# CPU.net
KiCad netlist of a schematic drawn in Altium Designer
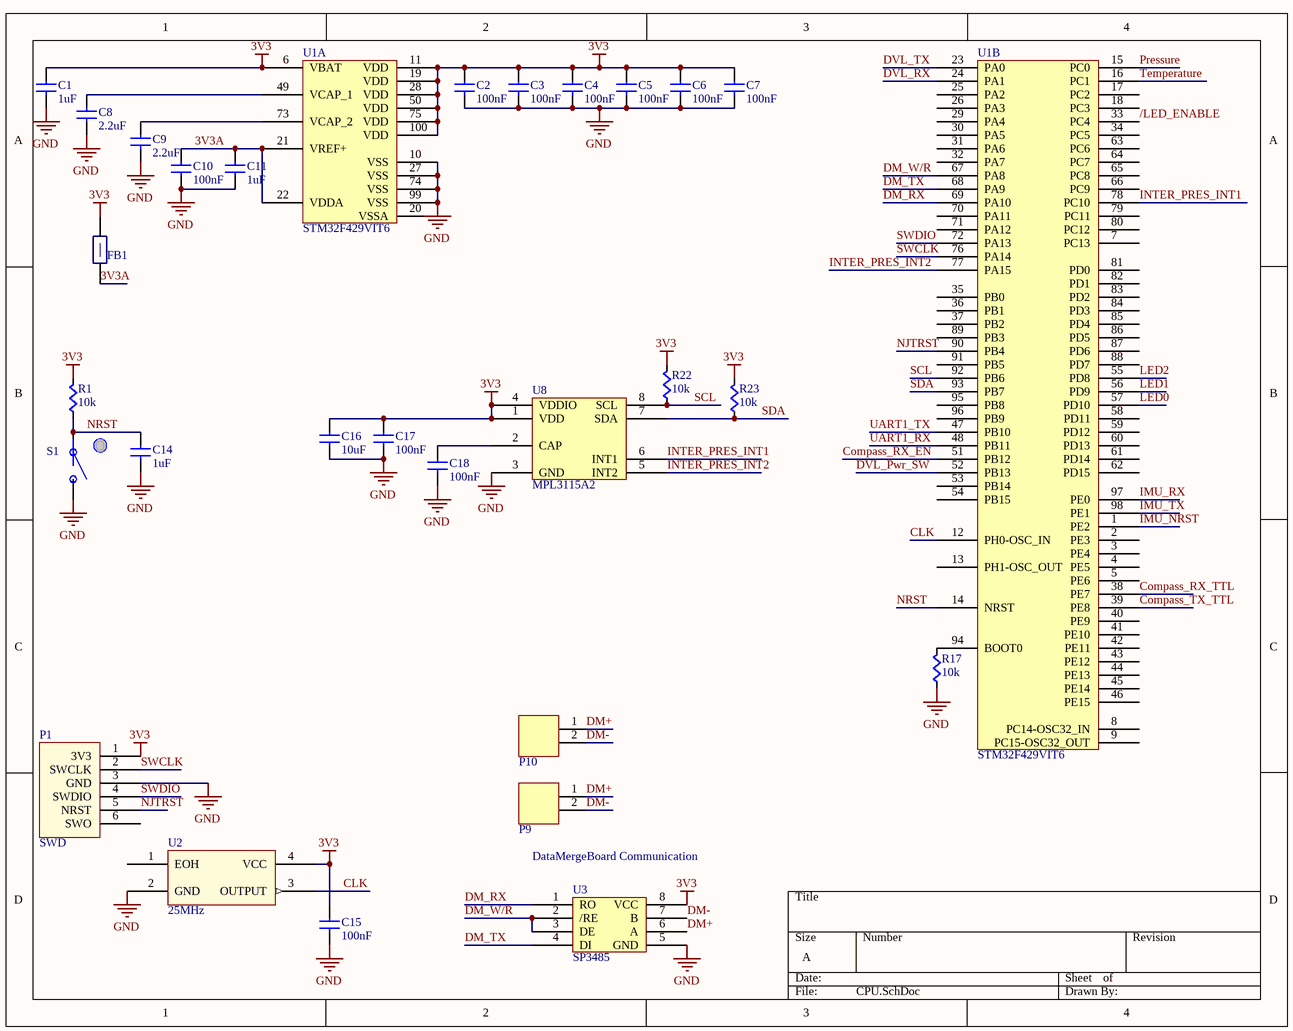
[diagram p0: CPU.SchDoc]

(export (version "E")
  (design (tool "Eeschema 10.0.6"))
  (components
    (comp (ref "C1")
      (value "1uF")
      (footprint "CAPC0603")
      (fields (field (name "Comment") "Cap"))
      (libsource (lib "SubjuGator8") (part "Cap"))
    )
    (comp (ref "C2")
      (value "100nF")
      (footprint "CAPC0603")
      (fields (field (name "Comment") "Cap"))
      (libsource (lib "SubjuGator8") (part "Cap"))
    )
    (comp (ref "C3")
      (value "100nF")
      (footprint "CAPC0603")
      (fields (field (name "Comment") "Cap"))
      (libsource (lib "SubjuGator8") (part "Cap"))
    )
    (comp (ref "C4")
      (value "100nF")
      (footprint "CAPC0603")
      (fields (field (name "Comment") "Cap"))
      (libsource (lib "SubjuGator8") (part "Cap"))
    )
    (comp (ref "C5")
      (value "100nF")
      (footprint "CAPC0603")
      (fields (field (name "Comment") "Cap"))
      (libsource (lib "SubjuGator8") (part "Cap"))
    )
    (comp (ref "C6")
      (value "100nF")
      (footprint "CAPC0603")
      (fields (field (name "Comment") "Cap"))
      (libsource (lib "SubjuGator8") (part "Cap"))
    )
    (comp (ref "C7")
      (value "100nF")
      (footprint "CAPC0603")
      (fields (field (name "Comment") "Cap"))
      (libsource (lib "SubjuGator8") (part "Cap"))
    )
    (comp (ref "C8")
      (value "2.2uF")
      (footprint "CAPC0603")
      (fields (field (name "Comment") "Cap"))
      (libsource (lib "SubjuGator8") (part "Cap"))
    )
    (comp (ref "C9")
      (value "2.2uF")
      (footprint "CAPC0603")
      (fields (field (name "Comment") "Cap"))
      (libsource (lib "SubjuGator8") (part "Cap"))
    )
    (comp (ref "C10")
      (value "100nF")
      (footprint "CAPC0603")
      (fields (field (name "Comment") "Cap"))
      (libsource (lib "SubjuGator8") (part "Cap"))
    )
    (comp (ref "C11")
      (value "1uF")
      (footprint "CAPC0603")
      (fields (field (name "Comment") "Cap"))
      (libsource (lib "SubjuGator8") (part "Cap"))
    )
    (comp (ref "C14")
      (value "1uF")
      (footprint "CAPC0603")
      (fields (field (name "Comment") "Cap"))
      (libsource (lib "SubjuGator8") (part "Cap"))
    )
    (comp (ref "C15")
      (value "100nF")
      (footprint "CAPC0603")
      (fields (field (name "Comment") "Cap"))
      (libsource (lib "SubjuGator8") (part "Cap"))
    )
    (comp (ref "C16")
      (value "10uF")
      (footprint "CAPC0603")
      (fields (field (name "Comment") "Cap"))
      (libsource (lib "SubjuGator8") (part "Cap"))
    )
    (comp (ref "C17")
      (value "100nF")
      (footprint "CAPC0603")
      (fields (field (name "Comment") "Cap"))
      (libsource (lib "SubjuGator8") (part "Cap"))
    )
    (comp (ref "C18")
      (value "100nF")
      (footprint "CAPC0603")
      (fields (field (name "Comment") "Cap"))
      (libsource (lib "SubjuGator8") (part "Cap"))
    )
    (comp (ref "FB1")
      (value "FBead")
      (footprint "RES0603")
      (description "Ferrite Bead")
      (libsource (lib "SubjuGator8") (part "FBead"))
    )
    (comp (ref "P1")
      (value "SWD")
      (footprint "SWD_STM32")
      (description "SWD connector matching the pinout on STM Discovery Boards")
      (libsource (lib "SubjuGator8") (part "SWD_STM32"))
    )
    (comp (ref "P9")
      (value "2-pin Horz Sherlock")
      (footprint "MOLEX-HDR-1X2-SHERLOCK-HORZ")
      (fields
        (field (name "MANUFACTURER PART NUMBER") "0353630260")
        (field (name "MANUFACTURER") "Molex Inc")
      )
      (libsource (lib "SubjuGator8") (part "MOLEX-HDR-1x2-SHERLOCK_RA"))
    )
    (comp (ref "P10")
      (value "2-pin Horz Sherlock")
      (footprint "MOLEX-HDR-1X2-SHERLOCK-HORZ")
      (fields
        (field (name "MANUFACTURER PART NUMBER") "0353630260")
        (field (name "MANUFACTURER") "Molex Inc")
      )
      (libsource (lib "SubjuGator8") (part "MOLEX-HDR-1x2-SHERLOCK_RA"))
    )
    (comp (ref "R1")
      (value "10k")
      (footprint "RES0603")
      (fields (field (name "Comment") "Res"))
      (libsource (lib "SubjuGator8") (part "Res"))
    )
    (comp (ref "R17")
      (value "10k")
      (footprint "RES0603")
      (fields (field (name "Comment") "Res"))
      (libsource (lib "SubjuGator8") (part "Res"))
    )
    (comp (ref "R22")
      (value "10k")
      (footprint "RES0603")
      (fields (field (name "Comment") "Res"))
      (libsource (lib "SubjuGator8") (part "Res"))
    )
    (comp (ref "R23")
      (value "10k")
      (footprint "RES0603")
      (fields (field (name "Comment") "Res"))
      (libsource (lib "SubjuGator8") (part "Res"))
    )
    (comp (ref "S1")
      (value "Button")
      (footprint "PTS645xxxxSMTR92")
      (description "SPST Button")
      (libsource (lib "SubjuGator8") (part "Button"))
    )
    (comp (ref "U1")
      (value "STM32F429VIT6")
      (footprint "STM32F429VIT6")
      (description "IC MCU ARM 2MB FLASH 100LQFP")
      (libsource (lib "ICs") (part "STM32F429VIT6"))
    )
    (comp (ref "U2")
      (value "25MHz")
      (footprint "636L3C")
      (description "HCMOS/TTL Clock Oscillator")
      (libsource (lib "SubjuGator8") (part "636L3C"))
    )
    (comp (ref "U3")
      (value "SP3485")
      (footprint "SP3485")
      (description "IC TXRX RS485 HALF DUPLEX 8NSOIC")
      (libsource (lib "SubjuGator8") (part "SP3485"))
    )
    (comp (ref "U8")
      (value "MPL3115A2")
      (footprint "MPL3115A2")
      (description "IC ALTIMETER I2C VERSION 8LGA")
      (libsource (lib "SubjuGator8") (part "MPL3115A2"))
    )
  )
  (nets
    (net (code "1") (name "/3V3A") (class "Default")
      (node (ref "C10") (pin "1") (pinfunction "A_1") (pintype "passive"))
      (node (ref "C11") (pin "1") (pinfunction "A_1") (pintype "passive"))
      (node (ref "FB1") (pin "1") (pinfunction "A_1") (pintype "passive"))
      (node (ref "U1") (pin "21") (pinfunction "VREF+_21") (pintype "passive"))
      (node (ref "U1") (pin "22") (pinfunction "VDDA_22") (pintype "passive"))
    )
    (net (code "2") (name "/CLK") (class "Default")
      (node (ref "U1") (pin "12") (pinfunction "PH0-OSC_IN_12") (pintype "passive"))
      (node (ref "U2") (pin "3") (pinfunction "OUTPUT_3") (pintype "output"))
    )
    (net (code "3") (name "/Compass_RX_EN") (class "Default")
      (node (ref "U1") (pin "51") (pinfunction "PB12_51") (pintype "passive"))
    )
    (net (code "4") (name "/Compass_RX_TTL") (class "Default")
      (node (ref "U1") (pin "38") (pinfunction "PE7_38") (pintype "passive"))
    )
    (net (code "5") (name "/Compass_TX_TTL") (class "Default")
      (node (ref "U1") (pin "39") (pinfunction "PE8_39") (pintype "passive"))
    )
    (net (code "6") (name "/DM+") (class "Default")
      (node (ref "P10") (pin "1") (pinfunction "1_1") (pintype "passive"))
      (node (ref "P9") (pin "1") (pinfunction "1_1") (pintype "passive"))
      (node (ref "U3") (pin "6") (pinfunction "A_6") (pintype "passive"))
    )
    (net (code "7") (name "/DM-") (class "Default")
      (node (ref "P10") (pin "2") (pinfunction "2_2") (pintype "passive"))
      (node (ref "P9") (pin "2") (pinfunction "2_2") (pintype "passive"))
      (node (ref "U3") (pin "7") (pinfunction "B_7") (pintype "passive"))
    )
    (net (code "8") (name "/DM_RX") (class "Default")
      (node (ref "U1") (pin "69") (pinfunction "PA10_69") (pintype "passive"))
      (node (ref "U3") (pin "1") (pinfunction "RO_1") (pintype "passive"))
    )
    (net (code "9") (name "/DM_TX") (class "Default")
      (node (ref "U1") (pin "68") (pinfunction "PA9_68") (pintype "passive"))
      (node (ref "U3") (pin "4") (pinfunction "DI_4") (pintype "passive"))
    )
    (net (code "10") (name "/DM_W{slash}R") (class "Default")
      (node (ref "U1") (pin "67") (pinfunction "PA8_67") (pintype "passive"))
      (node (ref "U3") (pin "2") (pinfunction "/RE_2") (pintype "passive"))
      (node (ref "U3") (pin "3") (pinfunction "DE_3") (pintype "passive"))
    )
    (net (code "11") (name "/DVL_Pwr_SW") (class "Default")
      (node (ref "U1") (pin "52") (pinfunction "PB13_52") (pintype "passive"))
    )
    (net (code "12") (name "/DVL_RX") (class "Default")
      (node (ref "U1") (pin "24") (pinfunction "PA1_24") (pintype "passive"))
    )
    (net (code "13") (name "/DVL_TX") (class "Default")
      (node (ref "U1") (pin "23") (pinfunction "PA0_23") (pintype "passive"))
    )
    (net (code "14") (name "/IMU_NRST") (class "Default")
      (node (ref "U1") (pin "1") (pinfunction "PE2_1") (pintype "passive"))
    )
    (net (code "15") (name "/IMU_RX") (class "Default")
      (node (ref "U1") (pin "97") (pinfunction "PE0_97") (pintype "passive"))
    )
    (net (code "16") (name "/IMU_TX") (class "Default")
      (node (ref "U1") (pin "98") (pinfunction "PE1_98") (pintype "passive"))
    )
    (net (code "17") (name "/INTER_PRES_INT1") (class "Default")
      (node (ref "U1") (pin "78") (pinfunction "PC10_78") (pintype "passive"))
      (node (ref "U8") (pin "6") (pinfunction "INT1_6") (pintype "passive"))
    )
    (net (code "18") (name "/INTER_PRES_INT2") (class "Default")
      (node (ref "U1") (pin "77") (pinfunction "PA15_77") (pintype "passive"))
      (node (ref "U8") (pin "5") (pinfunction "INT2_5") (pintype "passive"))
    )
    (net (code "19") (name "/LED0") (class "Default")
      (node (ref "U1") (pin "57") (pinfunction "PD10_57") (pintype "passive"))
    )
    (net (code "20") (name "/LED1") (class "Default")
      (node (ref "U1") (pin "56") (pinfunction "PD9_56") (pintype "passive"))
    )
    (net (code "21") (name "/LED2") (class "Default")
      (node (ref "U1") (pin "55") (pinfunction "PD8_55") (pintype "passive"))
    )
    (net (code "22") (name "/NJTRST") (class "Default")
      (node (ref "P1") (pin "5") (pinfunction "NRST_5") (pintype "passive"))
      (node (ref "U1") (pin "90") (pinfunction "PB4_90") (pintype "passive"))
    )
    (net (code "23") (name "/NRST") (class "Default")
      (node (ref "C14") (pin "1") (pinfunction "A_1") (pintype "passive"))
      (node (ref "R1") (pin "2") (pinfunction "B_2") (pintype "passive"))
      (node (ref "S1") (pin "A") (pinfunction "A_A") (pintype "passive"))
      (node (ref "U1") (pin "14") (pinfunction "NRST_14") (pintype "passive"))
    )
    (net (code "24") (name "/Pressure") (class "Default")
      (node (ref "U1") (pin "15") (pinfunction "PC0_15") (pintype "passive"))
    )
    (net (code "25") (name "/SCL") (class "Default")
      (node (ref "R22") (pin "2") (pinfunction "B_2") (pintype "passive"))
      (node (ref "U1") (pin "92") (pinfunction "PB6_92") (pintype "passive"))
      (node (ref "U8") (pin "8") (pinfunction "SCL_8") (pintype "passive"))
    )
    (net (code "26") (name "/SDA") (class "Default")
      (node (ref "R23") (pin "2") (pinfunction "B_2") (pintype "passive"))
      (node (ref "U1") (pin "93") (pinfunction "PB7_93") (pintype "passive"))
      (node (ref "U8") (pin "7") (pinfunction "SDA_7") (pintype "passive"))
    )
    (net (code "27") (name "/SWCLK") (class "Default")
      (node (ref "P1") (pin "2") (pinfunction "SWCLK_2") (pintype "passive"))
      (node (ref "U1") (pin "76") (pinfunction "PA14_76") (pintype "passive"))
    )
    (net (code "28") (name "/SWDIO") (class "Default")
      (node (ref "P1") (pin "4") (pinfunction "SWDIO_4") (pintype "passive"))
      (node (ref "U1") (pin "72") (pinfunction "PA13_72") (pintype "passive"))
    )
    (net (code "29") (name "/Temperature") (class "Default")
      (node (ref "U1") (pin "16") (pinfunction "PC1_16") (pintype "passive"))
    )
    (net (code "30") (name "/UART1_RX") (class "Default")
      (node (ref "U1") (pin "48") (pinfunction "PB11_48") (pintype "passive"))
    )
    (net (code "31") (name "/UART1_TX") (class "Default")
      (node (ref "U1") (pin "47") (pinfunction "PB10_47") (pintype "passive"))
    )
    (net (code "32") (name "/{slash}LED_ENABLE") (class "Default")
      (node (ref "U1") (pin "33") (pinfunction "PC4_33") (pintype "passive"))
    )
    (net (code "33") (name "3V3") (class "Default")
      (node (ref "C1") (pin "1") (pinfunction "A_1") (pintype "passive"))
      (node (ref "C15") (pin "1") (pinfunction "A_1") (pintype "passive"))
      (node (ref "C16") (pin "1") (pinfunction "A_1") (pintype "passive"))
      (node (ref "C17") (pin "1") (pinfunction "A_1") (pintype "passive"))
      (node (ref "C2") (pin "1") (pinfunction "A_1") (pintype "passive"))
      (node (ref "C3") (pin "1") (pinfunction "A_1") (pintype "passive"))
      (node (ref "C4") (pin "1") (pinfunction "A_1") (pintype "passive"))
      (node (ref "C5") (pin "1") (pinfunction "A_1") (pintype "passive"))
      (node (ref "C6") (pin "1") (pinfunction "A_1") (pintype "passive"))
      (node (ref "C7") (pin "1") (pinfunction "A_1") (pintype "passive"))
      (node (ref "FB1") (pin "2") (pinfunction "B_2") (pintype "passive"))
      (node (ref "P1") (pin "1") (pinfunction "3V3_1") (pintype "passive"))
      (node (ref "R1") (pin "1") (pinfunction "A_1") (pintype "passive"))
      (node (ref "R22") (pin "1") (pinfunction "A_1") (pintype "passive"))
      (node (ref "R23") (pin "1") (pinfunction "A_1") (pintype "passive"))
      (node (ref "U1") (pin "100") (pinfunction "VDD_100") (pintype "passive"))
      (node (ref "U1") (pin "11") (pinfunction "VDD_11") (pintype "passive"))
      (node (ref "U1") (pin "19") (pinfunction "VDD_19") (pintype "passive"))
      (node (ref "U1") (pin "28") (pinfunction "VDD_28") (pintype "passive"))
      (node (ref "U1") (pin "50") (pinfunction "VDD_50") (pintype "passive"))
      (node (ref "U1") (pin "6") (pinfunction "VBAT_6") (pintype "passive"))
      (node (ref "U1") (pin "75") (pinfunction "VDD_75") (pintype "passive"))
      (node (ref "U2") (pin "4") (pinfunction "VCC_4") (pintype "power_in"))
      (node (ref "U3") (pin "8") (pinfunction "VCC_8") (pintype "passive"))
      (node (ref "U8") (pin "1") (pinfunction "VDD_1") (pintype "passive"))
      (node (ref "U8") (pin "4") (pinfunction "VDDIO_4") (pintype "passive"))
    )
    (net (code "34") (name "GND") (class "Default")
      (node (ref "C1") (pin "2") (pinfunction "B_2") (pintype "passive"))
      (node (ref "C10") (pin "2") (pinfunction "B_2") (pintype "passive"))
      (node (ref "C11") (pin "2") (pinfunction "B_2") (pintype "passive"))
      (node (ref "C14") (pin "2") (pinfunction "B_2") (pintype "passive"))
      (node (ref "C15") (pin "2") (pinfunction "B_2") (pintype "passive"))
      (node (ref "C16") (pin "2") (pinfunction "B_2") (pintype "passive"))
      (node (ref "C17") (pin "2") (pinfunction "B_2") (pintype "passive"))
      (node (ref "C18") (pin "2") (pinfunction "B_2") (pintype "passive"))
      (node (ref "C2") (pin "2") (pinfunction "B_2") (pintype "passive"))
      (node (ref "C3") (pin "2") (pinfunction "B_2") (pintype "passive"))
      (node (ref "C4") (pin "2") (pinfunction "B_2") (pintype "passive"))
      (node (ref "C5") (pin "2") (pinfunction "B_2") (pintype "passive"))
      (node (ref "C6") (pin "2") (pinfunction "B_2") (pintype "passive"))
      (node (ref "C7") (pin "2") (pinfunction "B_2") (pintype "passive"))
      (node (ref "C8") (pin "2") (pinfunction "B_2") (pintype "passive"))
      (node (ref "C9") (pin "2") (pinfunction "B_2") (pintype "passive"))
      (node (ref "P1") (pin "3") (pinfunction "GND_3") (pintype "passive"))
      (node (ref "R17") (pin "2") (pinfunction "B_2") (pintype "passive"))
      (node (ref "S1") (pin "B") (pinfunction "B_B") (pintype "passive"))
      (node (ref "U1") (pin "10") (pinfunction "VSS_10") (pintype "passive"))
      (node (ref "U1") (pin "27") (pinfunction "VSS_27") (pintype "passive"))
      (node (ref "U1") (pin "74") (pinfunction "VSS_74") (pintype "passive"))
      (node (ref "U1") (pin "99") (pinfunction "VSS_99") (pintype "passive"))
      (node (ref "U2") (pin "2") (pinfunction "GND_2") (pintype "power_in"))
      (node (ref "U3") (pin "5") (pinfunction "GND_5") (pintype "passive"))
      (node (ref "U8") (pin "3") (pinfunction "GND_3") (pintype "passive"))
    )
    (net (code "35") (name "Net-(C8-A)") (class "Default")
      (node (ref "C8") (pin "1") (pinfunction "A_1") (pintype "passive"))
      (node (ref "U1") (pin "49") (pinfunction "VCAP_1_49") (pintype "passive"))
    )
    (net (code "36") (name "Net-(C9-A)") (class "Default")
      (node (ref "C9") (pin "1") (pinfunction "A_1") (pintype "passive"))
      (node (ref "U1") (pin "73") (pinfunction "VCAP_2_73") (pintype "passive"))
    )
    (net (code "37") (name "Net-(C18-A)") (class "Default")
      (node (ref "C18") (pin "1") (pinfunction "A_1") (pintype "passive"))
      (node (ref "U8") (pin "2") (pinfunction "CAP_2") (pintype "passive"))
    )
    (net (code "38") (name "Net-(R17-A)") (class "Default")
      (node (ref "R17") (pin "1") (pinfunction "A_1") (pintype "passive"))
      (node (ref "U1") (pin "94") (pinfunction "BOOT0_94") (pintype "passive"))
    )
    (net (code "39") (name "unconnected-(P1-SWO-Pad6)") (class "Default")
      (node (ref "P1") (pin "6") (pinfunction "SWO_6") (pintype "passive"))
    )
    (net (code "40") (name "unconnected-(U1A-VSSA-Pad20)") (class "Default")
      (node (ref "U1") (pin "20") (pinfunction "VSSA_20") (pintype "passive"))
    )
    (net (code "41") (name "unconnected-(U1B-PA2-Pad25)") (class "Default")
      (node (ref "U1") (pin "25") (pinfunction "PA2_25") (pintype "passive"))
    )
    (net (code "42") (name "unconnected-(U1B-PA3-Pad26)") (class "Default")
      (node (ref "U1") (pin "26") (pinfunction "PA3_26") (pintype "passive"))
    )
    (net (code "43") (name "unconnected-(U1B-PA4-Pad29)") (class "Default")
      (node (ref "U1") (pin "29") (pinfunction "PA4_29") (pintype "passive"))
    )
    (net (code "44") (name "unconnected-(U1B-PA5-Pad30)") (class "Default")
      (node (ref "U1") (pin "30") (pinfunction "PA5_30") (pintype "passive"))
    )
    (net (code "45") (name "unconnected-(U1B-PA6-Pad31)") (class "Default")
      (node (ref "U1") (pin "31") (pinfunction "PA6_31") (pintype "passive"))
    )
    (net (code "46") (name "unconnected-(U1B-PA7-Pad32)") (class "Default")
      (node (ref "U1") (pin "32") (pinfunction "PA7_32") (pintype "passive"))
    )
    (net (code "47") (name "unconnected-(U1B-PA11-Pad70)") (class "Default")
      (node (ref "U1") (pin "70") (pinfunction "PA11_70") (pintype "passive"))
    )
    (net (code "48") (name "unconnected-(U1B-PA12-Pad71)") (class "Default")
      (node (ref "U1") (pin "71") (pinfunction "PA12_71") (pintype "passive"))
    )
    (net (code "49") (name "unconnected-(U1B-PB0-Pad35)") (class "Default")
      (node (ref "U1") (pin "35") (pinfunction "PB0_35") (pintype "passive"))
    )
    (net (code "50") (name "unconnected-(U1B-PB1-Pad36)") (class "Default")
      (node (ref "U1") (pin "36") (pinfunction "PB1_36") (pintype "passive"))
    )
    (net (code "51") (name "unconnected-(U1B-PB2-Pad37)") (class "Default")
      (node (ref "U1") (pin "37") (pinfunction "PB2_37") (pintype "passive"))
    )
    (net (code "52") (name "unconnected-(U1B-PB3-Pad89)") (class "Default")
      (node (ref "U1") (pin "89") (pinfunction "PB3_89") (pintype "passive"))
    )
    (net (code "53") (name "unconnected-(U1B-PB5-Pad91)") (class "Default")
      (node (ref "U1") (pin "91") (pinfunction "PB5_91") (pintype "passive"))
    )
    (net (code "54") (name "unconnected-(U1B-PB8-Pad95)") (class "Default")
      (node (ref "U1") (pin "95") (pinfunction "PB8_95") (pintype "passive"))
    )
    (net (code "55") (name "unconnected-(U1B-PB9-Pad96)") (class "Default")
      (node (ref "U1") (pin "96") (pinfunction "PB9_96") (pintype "passive"))
    )
    (net (code "56") (name "unconnected-(U1B-PB14-Pad53)") (class "Default")
      (node (ref "U1") (pin "53") (pinfunction "PB14_53") (pintype "passive"))
    )
    (net (code "57") (name "unconnected-(U1B-PB15-Pad54)") (class "Default")
      (node (ref "U1") (pin "54") (pinfunction "PB15_54") (pintype "passive"))
    )
    (net (code "58") (name "unconnected-(U1B-PC2-Pad17)") (class "Default")
      (node (ref "U1") (pin "17") (pinfunction "PC2_17") (pintype "passive"))
    )
    (net (code "59") (name "unconnected-(U1B-PC3-Pad18)") (class "Default")
      (node (ref "U1") (pin "18") (pinfunction "PC3_18") (pintype "passive"))
    )
    (net (code "60") (name "unconnected-(U1B-PC5-Pad34)") (class "Default")
      (node (ref "U1") (pin "34") (pinfunction "PC5_34") (pintype "passive"))
    )
    (net (code "61") (name "unconnected-(U1B-PC6-Pad63)") (class "Default")
      (node (ref "U1") (pin "63") (pinfunction "PC6_63") (pintype "passive"))
    )
    (net (code "62") (name "unconnected-(U1B-PC7-Pad64)") (class "Default")
      (node (ref "U1") (pin "64") (pinfunction "PC7_64") (pintype "passive"))
    )
    (net (code "63") (name "unconnected-(U1B-PC8-Pad65)") (class "Default")
      (node (ref "U1") (pin "65") (pinfunction "PC8_65") (pintype "passive"))
    )
    (net (code "64") (name "unconnected-(U1B-PC9-Pad66)") (class "Default")
      (node (ref "U1") (pin "66") (pinfunction "PC9_66") (pintype "passive"))
    )
    (net (code "65") (name "unconnected-(U1B-PC11-Pad79)") (class "Default")
      (node (ref "U1") (pin "79") (pinfunction "PC11_79") (pintype "passive"))
    )
    (net (code "66") (name "unconnected-(U1B-PC12-Pad80)") (class "Default")
      (node (ref "U1") (pin "80") (pinfunction "PC12_80") (pintype "passive"))
    )
    (net (code "67") (name "unconnected-(U1B-PC13-Pad7)") (class "Default")
      (node (ref "U1") (pin "7") (pinfunction "PC13_7") (pintype "passive"))
    )
    (net (code "68") (name "unconnected-(U1B-PC14-OSC32_IN-Pad8)") (class "Default")
      (node (ref "U1") (pin "8") (pinfunction "PC14-OSC32_IN_8") (pintype "passive"))
    )
    (net (code "69") (name "unconnected-(U1B-PC15-OSC32_OUT-Pad9)") (class "Default")
      (node (ref "U1") (pin "9") (pinfunction "PC15-OSC32_OUT_9") (pintype "passive"))
    )
    (net (code "70") (name "unconnected-(U1B-PD0-Pad81)") (class "Default")
      (node (ref "U1") (pin "81") (pinfunction "PD0_81") (pintype "passive"))
    )
    (net (code "71") (name "unconnected-(U1B-PD1-Pad82)") (class "Default")
      (node (ref "U1") (pin "82") (pinfunction "PD1_82") (pintype "passive"))
    )
    (net (code "72") (name "unconnected-(U1B-PD2-Pad83)") (class "Default")
      (node (ref "U1") (pin "83") (pinfunction "PD2_83") (pintype "passive"))
    )
    (net (code "73") (name "unconnected-(U1B-PD3-Pad84)") (class "Default")
      (node (ref "U1") (pin "84") (pinfunction "PD3_84") (pintype "passive"))
    )
    (net (code "74") (name "unconnected-(U1B-PD4-Pad85)") (class "Default")
      (node (ref "U1") (pin "85") (pinfunction "PD4_85") (pintype "passive"))
    )
    (net (code "75") (name "unconnected-(U1B-PD5-Pad86)") (class "Default")
      (node (ref "U1") (pin "86") (pinfunction "PD5_86") (pintype "passive"))
    )
    (net (code "76") (name "unconnected-(U1B-PD6-Pad87)") (class "Default")
      (node (ref "U1") (pin "87") (pinfunction "PD6_87") (pintype "passive"))
    )
    (net (code "77") (name "unconnected-(U1B-PD7-Pad88)") (class "Default")
      (node (ref "U1") (pin "88") (pinfunction "PD7_88") (pintype "passive"))
    )
    (net (code "78") (name "unconnected-(U1B-PD11-Pad58)") (class "Default")
      (node (ref "U1") (pin "58") (pinfunction "PD11_58") (pintype "passive"))
    )
    (net (code "79") (name "unconnected-(U1B-PD12-Pad59)") (class "Default")
      (node (ref "U1") (pin "59") (pinfunction "PD12_59") (pintype "passive"))
    )
    (net (code "80") (name "unconnected-(U1B-PD13-Pad60)") (class "Default")
      (node (ref "U1") (pin "60") (pinfunction "PD13_60") (pintype "passive"))
    )
    (net (code "81") (name "unconnected-(U1B-PD14-Pad61)") (class "Default")
      (node (ref "U1") (pin "61") (pinfunction "PD14_61") (pintype "passive"))
    )
    (net (code "82") (name "unconnected-(U1B-PD15-Pad62)") (class "Default")
      (node (ref "U1") (pin "62") (pinfunction "PD15_62") (pintype "passive"))
    )
    (net (code "83") (name "unconnected-(U1B-PE3-Pad2)") (class "Default")
      (node (ref "U1") (pin "2") (pinfunction "PE3_2") (pintype "passive"))
    )
    (net (code "84") (name "unconnected-(U1B-PE4-Pad3)") (class "Default")
      (node (ref "U1") (pin "3") (pinfunction "PE4_3") (pintype "passive"))
    )
    (net (code "85") (name "unconnected-(U1B-PE5-Pad4)") (class "Default")
      (node (ref "U1") (pin "4") (pinfunction "PE5_4") (pintype "passive"))
    )
    (net (code "86") (name "unconnected-(U1B-PE6-Pad5)") (class "Default")
      (node (ref "U1") (pin "5") (pinfunction "PE6_5") (pintype "passive"))
    )
    (net (code "87") (name "unconnected-(U1B-PE9-Pad40)") (class "Default")
      (node (ref "U1") (pin "40") (pinfunction "PE9_40") (pintype "passive"))
    )
    (net (code "88") (name "unconnected-(U1B-PE10-Pad41)") (class "Default")
      (node (ref "U1") (pin "41") (pinfunction "PE10_41") (pintype "passive"))
    )
    (net (code "89") (name "unconnected-(U1B-PE11-Pad42)") (class "Default")
      (node (ref "U1") (pin "42") (pinfunction "PE11_42") (pintype "passive"))
    )
    (net (code "90") (name "unconnected-(U1B-PE12-Pad43)") (class "Default")
      (node (ref "U1") (pin "43") (pinfunction "PE12_43") (pintype "passive"))
    )
    (net (code "91") (name "unconnected-(U1B-PE13-Pad44)") (class "Default")
      (node (ref "U1") (pin "44") (pinfunction "PE13_44") (pintype "passive"))
    )
    (net (code "92") (name "unconnected-(U1B-PE14-Pad45)") (class "Default")
      (node (ref "U1") (pin "45") (pinfunction "PE14_45") (pintype "passive"))
    )
    (net (code "93") (name "unconnected-(U1B-PE15-Pad46)") (class "Default")
      (node (ref "U1") (pin "46") (pinfunction "PE15_46") (pintype "passive"))
    )
    (net (code "94") (name "unconnected-(U1B-PH1-OSC_OUT-Pad13)") (class "Default")
      (node (ref "U1") (pin "13") (pinfunction "PH1-OSC_OUT_13") (pintype "passive"))
    )
    (net (code "95") (name "unconnected-(U2-EOH-Pad1)") (class "Default")
      (node (ref "U2") (pin "1") (pinfunction "EOH_1") (pintype "passive"))
    )
  )
)
